# Sheet1.net
KiCad netlist of a schematic drawn in Altium Designer
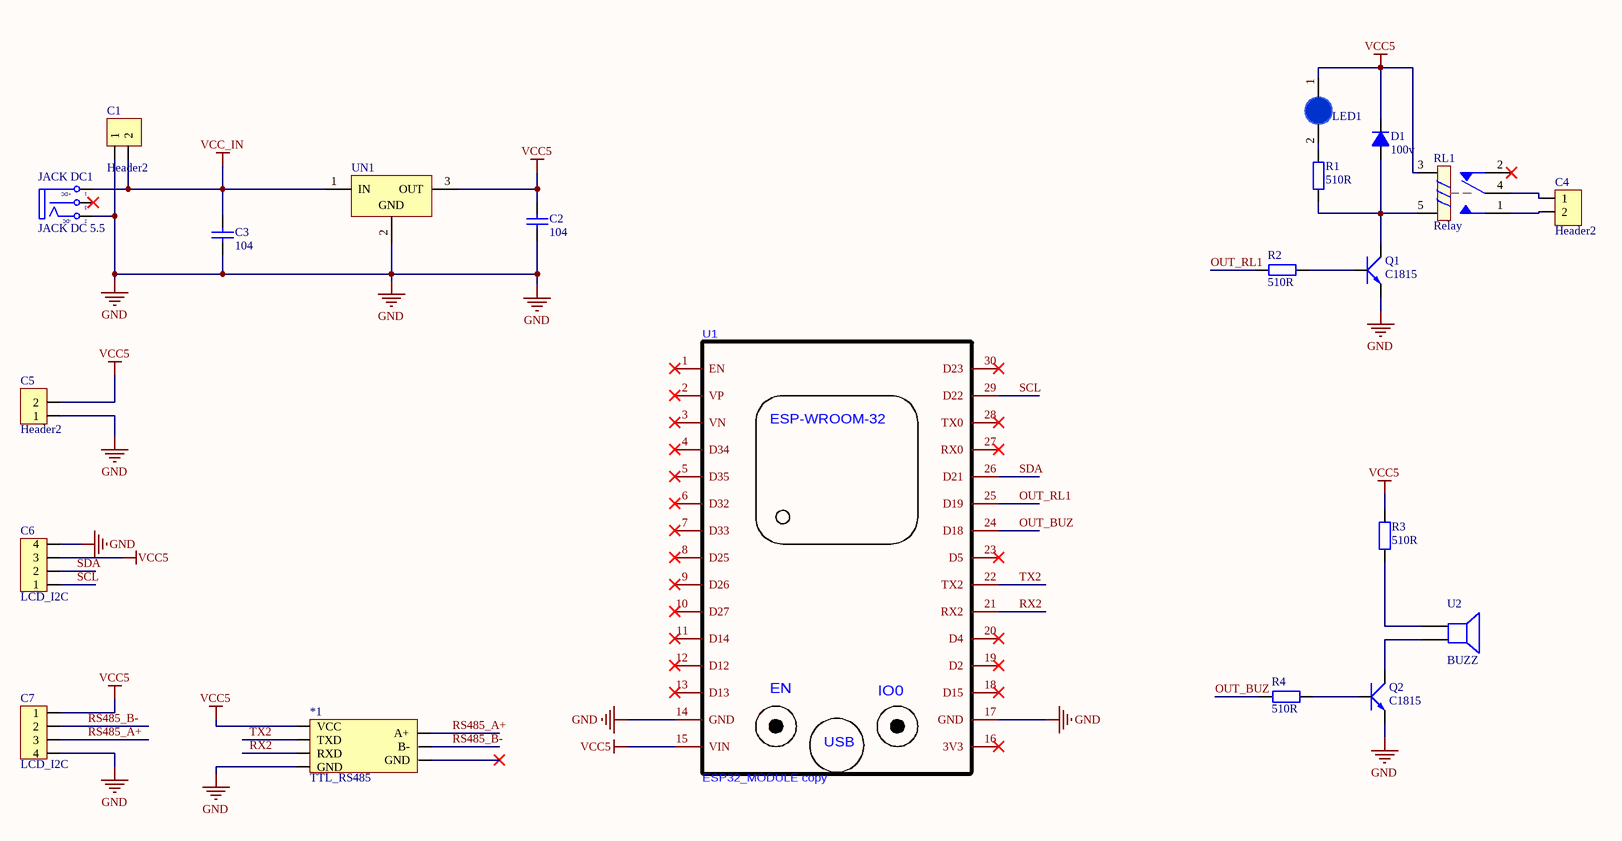
[diagram p0: Sheet1.SchDoc]

(export (version "E")
  (design (tool "Eeschema 10.0.6"))
  (components
    (comp (ref "*1")
      (value "TTL_RS485")
      (footprint "RS-485 Module")
      (libsource (lib "myLib_v1") (part "TTL_RS485"))
    )
    (comp (ref "C1")
      (value "Header2")
      (footprint "Header2")
      (description "Header IDC, 2 x 1 Pin Vertical 2.54mm Pitch (Non-Boxed, Male)")
      (fields
        (field (name "MANUFACTURER") "Würth Elektronik eiSos GmbH")
        (field (name "PARTNO") "613002143121")
        (field (name "CREATED BY") "Karrer Zheng")
      )
      (libsource (lib "") (part "Header2_1"))
    )
    (comp (ref "C2")
      (value "104")
      (footprint "tu gom")
      (description "Cắm")
      (libsource (lib "Altium_Lib_by_KhueNguyenCreator") (part "Tu gom 104 50V"))
    )
    (comp (ref "C3")
      (value "104")
      (footprint "tu gom")
      (description "Cắm")
      (libsource (lib "Altium_Lib_by_KhueNguyenCreator") (part "Tu gom 104 50V"))
    )
    (comp (ref "C4")
      (value "Header2")
      (footprint "Header2")
      (description "Header IDC, 2 x 1 Pin Vertical 2.54mm Pitch (Non-Boxed, Male)")
      (fields
        (field (name "MANUFACTURER") "Würth Elektronik eiSos GmbH")
        (field (name "PARTNO") "613002143121")
        (field (name "CREATED BY") "Karrer Zheng")
      )
      (libsource (lib "myLib_v1") (part "Header2"))
    )
    (comp (ref "C5")
      (value "Header2")
      (footprint "Header2")
      (description "Header IDC, 2 x 1 Pin Vertical 2.54mm Pitch (Non-Boxed, Male)")
      (fields
        (field (name "MANUFACTURER") "Würth Elektronik eiSos GmbH")
        (field (name "PARTNO") "613002143121")
        (field (name "CREATED BY") "Karrer Zheng")
      )
      (libsource (lib "") (part "Header2_2"))
    )
    (comp (ref "C6")
      (value "LCD_I2C")
      (footprint "Header4")
      (description "Header IDC, 4 x 1 Pin Vertical 2.54mm Pitch (Non-Boxed, Male)")
      (fields
        (field (name "MANUFACTURER") "Würth Elektronik eiSos GmbH")
        (field (name "PARTNO") "613002143121")
        (field (name "CREATED BY") "Karrer Zheng")
      )
      (libsource (lib "myLib_v1") (part "Header4"))
    )
    (comp (ref "C7")
      (value "LCD_I2C")
      (footprint "Header4")
      (description "Header IDC, 4 x 1 Pin Vertical 2.54mm Pitch (Non-Boxed, Male)")
      (fields
        (field (name "MANUFACTURER") "Würth Elektronik eiSos GmbH")
        (field (name "PARTNO") "613002143121")
        (field (name "CREATED BY") "Karrer Zheng")
      )
      (libsource (lib "") (part "Header4_1"))
    )
    (comp (ref "D1")
      (value "100v")
      (footprint "DIODE 0.5A")
      (description "Cắm")
      (libsource (lib "Altium_Lib_by_KhueNguyenCreator") (part "Diode 1N4148"))
    )
    (comp (ref "JACK DC1")
      (value "JACK DC 5.5")
      (footprint "JACK DC 5.5")
      (libsource (lib "Altium_Lib_by_KhueNguyenCreator") (part "JACK DC 5.5"))
    )
    (comp (ref "LED1")
      (value "LED 3mm")
      (footprint "LED-3MM-BLUE")
      (description "Cắm")
      (libsource (lib "myLib_v1") (part "LED 3mm Xanh Duong"))
    )
    (comp (ref "Q1")
      (value "C1815")
      (footprint "C1815_cam")
      (description "NPN 600mW, ECB")
      (libsource (lib "myLib_v1") (part "C1815"))
    )
    (comp (ref "Q2")
      (value "C1815")
      (footprint "C1815_cam")
      (description "NPN 600mW, ECB")
      (libsource (lib "myLib_v1") (part "C1815"))
    )
    (comp (ref "R1")
      (value "510R")
      (footprint "R1/4W")
      (description "Resistor 1/4W")
      (libsource (lib "myLib_v1") (part "R1/4W"))
    )
    (comp (ref "R2")
      (value "510R")
      (footprint "R1/4W")
      (description "Resistor 1/4W")
      (libsource (lib "myLib_v1") (part "R1/4W"))
    )
    (comp (ref "R3")
      (value "510R")
      (footprint "R1/4W")
      (description "Resistor 1/4W")
      (libsource (lib "myLib_v1") (part "R1/4W"))
    )
    (comp (ref "R4")
      (value "510R")
      (footprint "R1/4W")
      (description "Resistor 1/4W")
      (libsource (lib "myLib_v1") (part "R1/4W"))
    )
    (comp (ref "RL1")
      (value "Relay")
      (footprint "RELAY_SRA_05VDC_SL_C")
      (description "Relay 5 Chan")
      (libsource (lib "myLib_v1") (part "RL_SRA-05VDC-SL-C"))
    )
    (comp (ref "U1")
      (value "ESP32_MODULE copy")
      (footprint "ESP32-WIFIMODULE-FOOTPRINT")
      (libsource (lib "myLib_v1") (part "ESP32_MODULE copy"))
    )
    (comp (ref "U2")
      (value "BUZZ")
      (footprint "BUZZER_D9_TH")
      (description "Loudspeaker")
      (libsource (lib "BYTECH_HW_LIB_2019 (1)") (part "Speaker"))
    )
    (comp (ref "UN1")
      (value "L78M05CP")
      (footprint "QTO-220H2")
      (description "Positive Voltage Regulator")
      (fields (field (name "PUBLISHER") "Altium Limited"))
      (libsource (lib "syhaunguyen") (part "L78M05CP"))
    )
  )
  (nets
    (net (code "1") (name "/OUT_BUZ") (class "Default")
      (node (ref "R4") (pin "1") (pinfunction "1_1") (pintype "passive"))
      (node (ref "U1") (pin "24") (pinfunction "D18_24") (pintype "passive"))
    )
    (net (code "2") (name "/OUT_RL1") (class "Default")
      (node (ref "R2") (pin "1") (pinfunction "1_1") (pintype "passive"))
      (node (ref "U1") (pin "25") (pinfunction "D19_25") (pintype "passive"))
    )
    (net (code "3") (name "/RS485_A+") (class "Default")
      (node (ref "*1") (pin "7") (pinfunction "A+_7") (pintype "passive"))
      (node (ref "C7") (pin "3") (pinfunction "3_3") (pintype "passive"))
    )
    (net (code "4") (name "/RS485_B-") (class "Default")
      (node (ref "*1") (pin "6") (pinfunction "B-_6") (pintype "passive"))
      (node (ref "C7") (pin "2") (pinfunction "2_2") (pintype "passive"))
    )
    (net (code "5") (name "/RX2") (class "Default")
      (node (ref "*1") (pin "3") (pinfunction "RXD_3") (pintype "passive"))
      (node (ref "U1") (pin "21") (pinfunction "RX2_21") (pintype "passive"))
    )
    (net (code "6") (name "/SCL") (class "Default")
      (node (ref "C6") (pin "1") (pinfunction "1_1") (pintype "passive"))
      (node (ref "U1") (pin "29") (pinfunction "D22_29") (pintype "passive"))
    )
    (net (code "7") (name "/SDA") (class "Default")
      (node (ref "C6") (pin "2") (pinfunction "2_2") (pintype "passive"))
      (node (ref "U1") (pin "26") (pinfunction "D21_26") (pintype "passive"))
    )
    (net (code "8") (name "/TX2") (class "Default")
      (node (ref "*1") (pin "2") (pinfunction "TXD_2") (pintype "passive"))
      (node (ref "U1") (pin "22") (pinfunction "TX2_22") (pintype "passive"))
    )
    (net (code "9") (name "GND") (class "Default")
      (node (ref "*1") (pin "4") (pinfunction "GND_4") (pintype "passive"))
      (node (ref "C1") (pin "1") (pinfunction "1_1") (pintype "passive"))
      (node (ref "C2") (pin "2") (pinfunction "2_2") (pintype "passive"))
      (node (ref "C3") (pin "2") (pinfunction "2_2") (pintype "passive"))
      (node (ref "C5") (pin "1") (pinfunction "1_1") (pintype "passive"))
      (node (ref "C6") (pin "4") (pinfunction "4_4") (pintype "passive"))
      (node (ref "C7") (pin "4") (pinfunction "4_4") (pintype "passive"))
      (node (ref "JACK DC1") (pin "2") (pinfunction "TN_2") (pintype "passive"))
      (node (ref "Q1") (pin "1") (pinfunction "E_1") (pintype "passive"))
      (node (ref "Q2") (pin "1") (pinfunction "E_1") (pintype "passive"))
      (node (ref "U1") (pin "14") (pinfunction "GND_14") (pintype "passive"))
      (node (ref "U1") (pin "17") (pinfunction "GND_17") (pintype "passive"))
      (node (ref "UN1") (pin "2") (pinfunction "GND_2") (pintype "power_in"))
    )
    (net (code "10") (name "Net-(C4-Pad1)") (class "Default")
      (node (ref "C4") (pin "1") (pinfunction "1_1") (pintype "passive"))
      (node (ref "RL1") (pin "4") (pinfunction "4_4") (pintype "passive"))
    )
    (net (code "11") (name "Net-(C4-Pad2)") (class "Default")
      (node (ref "C4") (pin "2") (pinfunction "2_2") (pintype "passive"))
      (node (ref "RL1") (pin "1") (pinfunction "1_1") (pintype "passive"))
    )
    (net (code "12") (name "Net-(D1-A)") (class "Default")
      (node (ref "D1") (pin "1") (pinfunction "A_1") (pintype "passive"))
      (node (ref "Q1") (pin "2") (pinfunction "C_2") (pintype "passive"))
      (node (ref "R1") (pin "2") (pinfunction "2_2") (pintype "passive"))
      (node (ref "RL1") (pin "5") (pinfunction "5_5") (pintype "passive"))
    )
    (net (code "13") (name "Net-(LED1-K)") (class "Default")
      (node (ref "LED1") (pin "2") (pinfunction "K_2") (pintype "passive"))
      (node (ref "R1") (pin "1") (pinfunction "1_1") (pintype "passive"))
    )
    (net (code "14") (name "Net-(Q1-B)") (class "Default")
      (node (ref "Q1") (pin "3") (pinfunction "B_3") (pintype "passive"))
      (node (ref "R2") (pin "2") (pinfunction "2_2") (pintype "passive"))
    )
    (net (code "15") (name "Net-(Q2-B)") (class "Default")
      (node (ref "Q2") (pin "3") (pinfunction "B_3") (pintype "passive"))
      (node (ref "R4") (pin "2") (pinfunction "2_2") (pintype "passive"))
    )
    (net (code "16") (name "Net-(Q2-C)") (class "Default")
      (node (ref "Q2") (pin "2") (pinfunction "C_2") (pintype "passive"))
      (node (ref "U2") (pin "2") (pinfunction "2_2") (pintype "passive"))
    )
    (net (code "17") (name "Net-(R3-Pad2)") (class "Default")
      (node (ref "R3") (pin "2") (pinfunction "2_2") (pintype "passive"))
      (node (ref "U2") (pin "1") (pinfunction "1_1") (pintype "passive"))
    )
    (net (code "18") (name "VCC5") (class "Default")
      (node (ref "*1") (pin "1") (pinfunction "VCC_1") (pintype "passive"))
      (node (ref "C2") (pin "1") (pinfunction "1_1") (pintype "passive"))
      (node (ref "C5") (pin "2") (pinfunction "2_2") (pintype "passive"))
      (node (ref "C6") (pin "3") (pinfunction "3_3") (pintype "passive"))
      (node (ref "C7") (pin "1") (pinfunction "1_1") (pintype "passive"))
      (node (ref "D1") (pin "2") (pinfunction "K_2") (pintype "passive"))
      (node (ref "LED1") (pin "1") (pinfunction "A_1") (pintype "passive"))
      (node (ref "R3") (pin "1") (pinfunction "1_1") (pintype "passive"))
      (node (ref "RL1") (pin "3") (pinfunction "3_3") (pintype "passive"))
      (node (ref "U1") (pin "15") (pinfunction "VIN_15") (pintype "passive"))
      (node (ref "UN1") (pin "3") (pinfunction "OUT_3") (pintype "power_in"))
    )
    (net (code "19") (name "VCC_IN") (class "Default")
      (node (ref "C1") (pin "2") (pinfunction "2_2") (pintype "passive"))
      (node (ref "C3") (pin "1") (pinfunction "1_1") (pintype "passive"))
      (node (ref "JACK DC1") (pin "1") (pinfunction "T_1") (pintype "passive"))
      (node (ref "UN1") (pin "1") (pinfunction "IN_1") (pintype "power_in"))
    )
    (net (code "20") (name "unconnected-(*1-GND-Pad5)") (class "Default")
      (node (ref "*1") (pin "5") (pinfunction "GND_5") (pintype "passive+no_connect"))
    )
    (net (code "21") (name "unconnected-(JACK DC1-S-Pad3)") (class "Default")
      (node (ref "JACK DC1") (pin "3") (pinfunction "S_3") (pintype "power_in+no_connect"))
    )
    (net (code "22") (name "unconnected-(RL1-Pad2)") (class "Default")
      (node (ref "RL1") (pin "2") (pinfunction "2_2") (pintype "passive+no_connect"))
    )
    (net (code "23") (name "unconnected-(U1-3V3-Pad16)") (class "Default")
      (node (ref "U1") (pin "16") (pinfunction "3V3_16") (pintype "passive+no_connect"))
    )
    (net (code "24") (name "unconnected-(U1-D2-Pad19)") (class "Default")
      (node (ref "U1") (pin "19") (pinfunction "D2_19") (pintype "passive+no_connect"))
    )
    (net (code "25") (name "unconnected-(U1-D4-Pad20)") (class "Default")
      (node (ref "U1") (pin "20") (pinfunction "D4_20") (pintype "passive+no_connect"))
    )
    (net (code "26") (name "unconnected-(U1-D5-Pad23)") (class "Default")
      (node (ref "U1") (pin "23") (pinfunction "D5_23") (pintype "passive+no_connect"))
    )
    (net (code "27") (name "unconnected-(U1-D12-Pad12)") (class "Default")
      (node (ref "U1") (pin "12") (pinfunction "D12_12") (pintype "passive+no_connect"))
    )
    (net (code "28") (name "unconnected-(U1-D13-Pad13)") (class "Default")
      (node (ref "U1") (pin "13") (pinfunction "D13_13") (pintype "passive+no_connect"))
    )
    (net (code "29") (name "unconnected-(U1-D14-Pad11)") (class "Default")
      (node (ref "U1") (pin "11") (pinfunction "D14_11") (pintype "passive+no_connect"))
    )
    (net (code "30") (name "unconnected-(U1-D15-Pad18)") (class "Default")
      (node (ref "U1") (pin "18") (pinfunction "D15_18") (pintype "passive+no_connect"))
    )
    (net (code "31") (name "unconnected-(U1-D23-Pad30)") (class "Default")
      (node (ref "U1") (pin "30") (pinfunction "D23_30") (pintype "passive+no_connect"))
    )
    (net (code "32") (name "unconnected-(U1-D25-Pad8)") (class "Default")
      (node (ref "U1") (pin "8") (pinfunction "D25_8") (pintype "passive+no_connect"))
    )
    (net (code "33") (name "unconnected-(U1-D26-Pad9)") (class "Default")
      (node (ref "U1") (pin "9") (pinfunction "D26_9") (pintype "passive+no_connect"))
    )
    (net (code "34") (name "unconnected-(U1-D27-Pad10)") (class "Default")
      (node (ref "U1") (pin "10") (pinfunction "D27_10") (pintype "passive+no_connect"))
    )
    (net (code "35") (name "unconnected-(U1-D32-Pad6)") (class "Default")
      (node (ref "U1") (pin "6") (pinfunction "D32_6") (pintype "passive+no_connect"))
    )
    (net (code "36") (name "unconnected-(U1-D33-Pad7)") (class "Default")
      (node (ref "U1") (pin "7") (pinfunction "D33_7") (pintype "passive+no_connect"))
    )
    (net (code "37") (name "unconnected-(U1-D34-Pad4)") (class "Default")
      (node (ref "U1") (pin "4") (pinfunction "D34_4") (pintype "passive+no_connect"))
    )
    (net (code "38") (name "unconnected-(U1-D35-Pad5)") (class "Default")
      (node (ref "U1") (pin "5") (pinfunction "D35_5") (pintype "passive+no_connect"))
    )
    (net (code "39") (name "unconnected-(U1-EN-Pad1)") (class "Default")
      (node (ref "U1") (pin "1") (pinfunction "EN_1") (pintype "passive+no_connect"))
    )
    (net (code "40") (name "unconnected-(U1-RX0-Pad27)") (class "Default")
      (node (ref "U1") (pin "27") (pinfunction "RX0_27") (pintype "passive+no_connect"))
    )
    (net (code "41") (name "unconnected-(U1-TX0-Pad28)") (class "Default")
      (node (ref "U1") (pin "28") (pinfunction "TX0_28") (pintype "passive+no_connect"))
    )
    (net (code "42") (name "unconnected-(U1-VN-Pad3)") (class "Default")
      (node (ref "U1") (pin "3") (pinfunction "VN_3") (pintype "passive+no_connect"))
    )
    (net (code "43") (name "unconnected-(U1-VP-Pad2)") (class "Default")
      (node (ref "U1") (pin "2") (pinfunction "VP_2") (pintype "passive+no_connect"))
    )
  )
)
